# isd_main_lighting_board.net
KiCad netlist of a schematic drawn in EAGLE
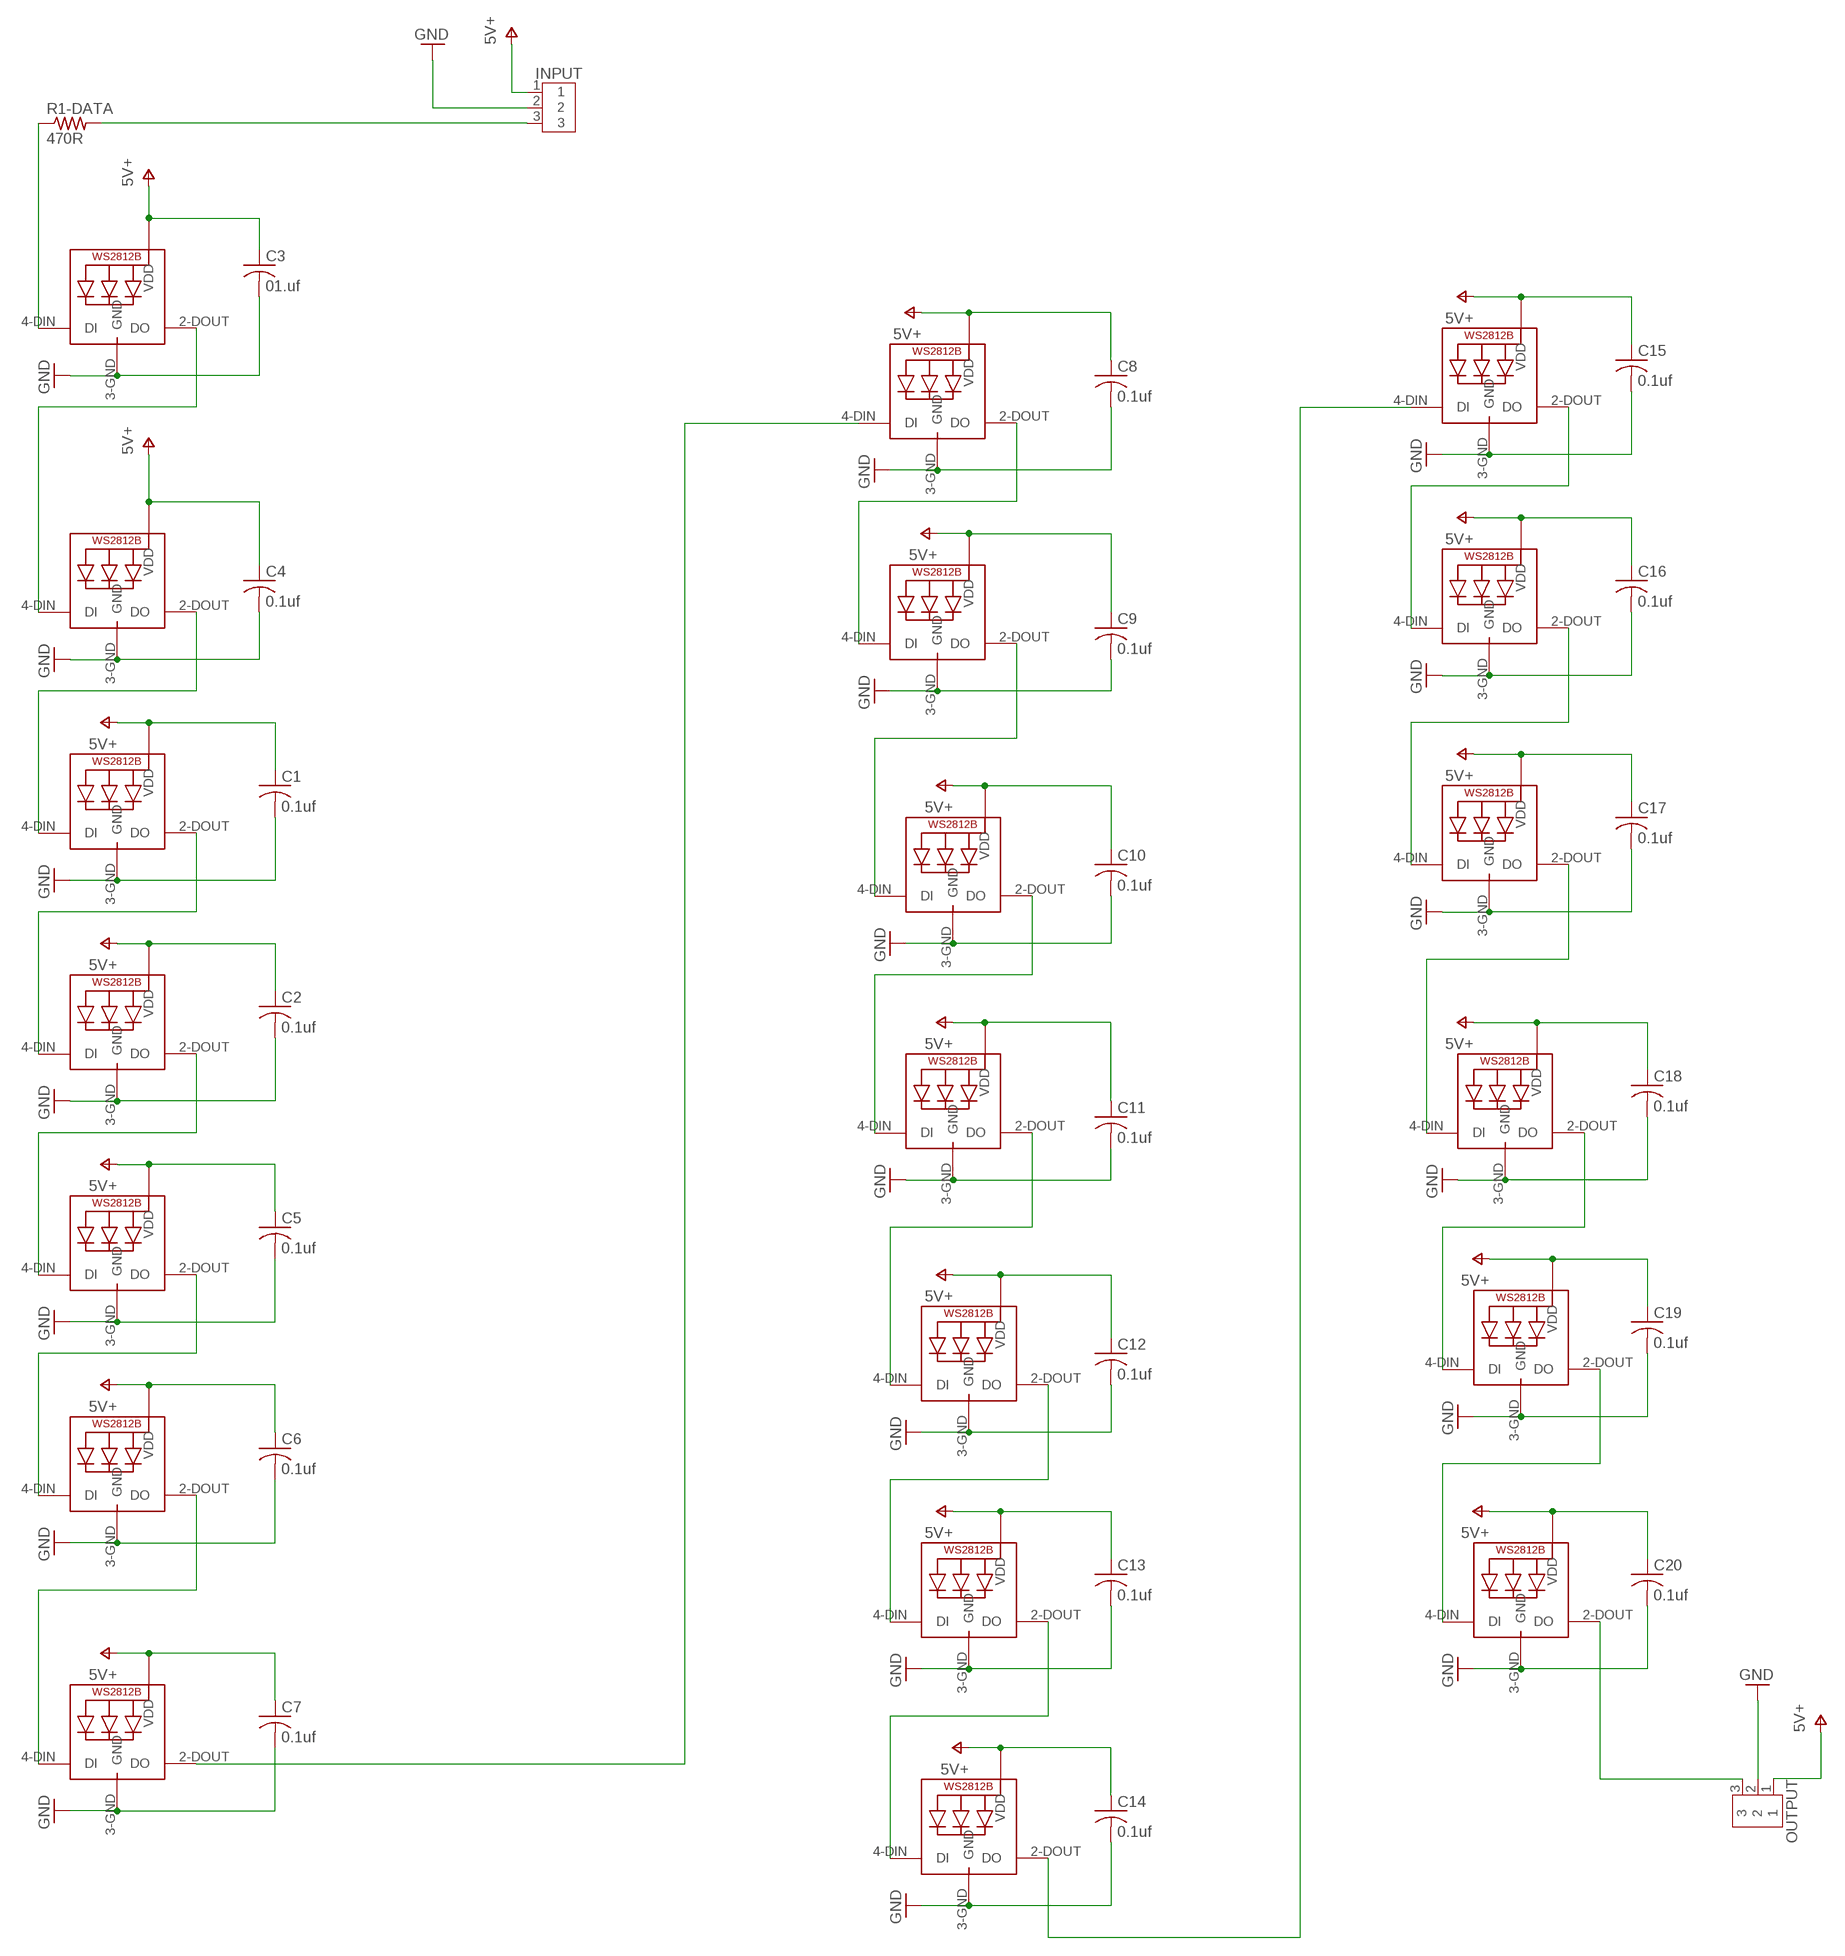
[diagram p0: schematic, sheet 1]

(export (version "E")
  (design (tool "Eeschema 10.0.6"))
  (components
    (comp (ref "C1")
      (value "0.1uf")
      (footprint "eagle-import:C0805K")
      (libsource (lib "eagle-import") (part "C-USC0805K"))
    )
    (comp (ref "C2")
      (value "0.1uf")
      (footprint "eagle-import:C0805K")
      (libsource (lib "eagle-import") (part "C-USC0805K"))
    )
    (comp (ref "C3")
      (value "01.uf")
      (footprint "eagle-import:C0805K")
      (libsource (lib "eagle-import") (part "C-USC0805K"))
    )
    (comp (ref "C4")
      (value "0.1uf")
      (footprint "eagle-import:C0805K")
      (libsource (lib "eagle-import") (part "C-USC0805K"))
    )
    (comp (ref "C5")
      (value "0.1uf")
      (footprint "eagle-import:C0805K")
      (libsource (lib "eagle-import") (part "C-USC0805K"))
    )
    (comp (ref "C6")
      (value "0.1uf")
      (footprint "eagle-import:C0805K")
      (libsource (lib "eagle-import") (part "C-USC0805K"))
    )
    (comp (ref "C7")
      (value "0.1uf")
      (footprint "eagle-import:C0805K")
      (libsource (lib "eagle-import") (part "C-USC0805K"))
    )
    (comp (ref "C8")
      (value "0.1uf")
      (footprint "eagle-import:C0805K")
      (libsource (lib "eagle-import") (part "C-USC0805K"))
    )
    (comp (ref "C9")
      (value "0.1uf")
      (footprint "eagle-import:C0805K")
      (libsource (lib "eagle-import") (part "C-USC0805K"))
    )
    (comp (ref "C10")
      (value "0.1uf")
      (footprint "eagle-import:C0805K")
      (libsource (lib "eagle-import") (part "C-USC0805K"))
    )
    (comp (ref "C11")
      (value "0.1uf")
      (footprint "eagle-import:C0805K")
      (libsource (lib "eagle-import") (part "C-USC0805K"))
    )
    (comp (ref "C12")
      (value "0.1uf")
      (footprint "eagle-import:C0805K")
      (libsource (lib "eagle-import") (part "C-USC0805K"))
    )
    (comp (ref "C13")
      (value "0.1uf")
      (footprint "eagle-import:C0805K")
      (libsource (lib "eagle-import") (part "C-USC0805K"))
    )
    (comp (ref "C14")
      (value "0.1uf")
      (footprint "eagle-import:C0805K")
      (libsource (lib "eagle-import") (part "C-USC0805K"))
    )
    (comp (ref "C15")
      (value "0.1uf")
      (footprint "eagle-import:C0805K")
      (libsource (lib "eagle-import") (part "C-USC0805K"))
    )
    (comp (ref "C16")
      (value "0.1uf")
      (footprint "eagle-import:C0805K")
      (libsource (lib "eagle-import") (part "C-USC0805K"))
    )
    (comp (ref "C17")
      (value "0.1uf")
      (footprint "eagle-import:C0805K")
      (libsource (lib "eagle-import") (part "C-USC0805K"))
    )
    (comp (ref "C18")
      (value "0.1uf")
      (footprint "eagle-import:C0805K")
      (libsource (lib "eagle-import") (part "C-USC0805K"))
    )
    (comp (ref "C19")
      (value "0.1uf")
      (footprint "eagle-import:C0805K")
      (libsource (lib "eagle-import") (part "C-USC0805K"))
    )
    (comp (ref "C20")
      (value "0.1uf")
      (footprint "eagle-import:C0805K")
      (libsource (lib "eagle-import") (part "C-USC0805K"))
    )
    (comp (ref "INPUT")
      (value "B3B-XH-A")
      (footprint "eagle-import:B3B-XH-A")
      (fields (field (name "MANUFACTURER") "JST (XH connector)") (field (name "SPICEPREFIX") "X"))
      (libsource (lib "eagle-import") (part "B3B-XH-A"))
    )
    (comp (ref "OUTPUT")
      (value "B3B-XH-A")
      (footprint "eagle-import:B3B-XH-A")
      (fields (field (name "MANUFACTURER") "JST (XH connector)") (field (name "SPICEPREFIX") "X"))
      (libsource (lib "eagle-import") (part "B3B-XH-A"))
    )
    (comp (ref "R1-DATA")
      (value "470R")
      (footprint "eagle-import:0204_5")
      (fields (field (name "SPICEPREFIX") "R"))
      (libsource (lib "eagle-import") (part "R-US_0204/5"))
    )
    (comp (ref "RGB1")
      (value "WS2812B_5050N")
      (footprint "eagle-import:WS2812B-NARROW")
      (libsource (lib "eagle-import") (part "WS2812B_5050N"))
    )
    (comp (ref "RGB2")
      (value "WS2812B_5050N")
      (footprint "eagle-import:WS2812B-NARROW")
      (fields (field (name "SPICEPREFIX") "E"))
      (libsource (lib "eagle-import") (part "WS2812B_5050N"))
    )
    (comp (ref "RGB3")
      (value "WS2812B_5050N")
      (footprint "eagle-import:WS2812B-NARROW")
      (fields (field (name "SPICEPREFIX") "E"))
      (libsource (lib "eagle-import") (part "WS2812B_5050N"))
    )
    (comp (ref "RGB4")
      (value "WS2812B_5050N")
      (footprint "eagle-import:WS2812B-NARROW")
      (fields (field (name "SPICEPREFIX") "E"))
      (libsource (lib "eagle-import") (part "WS2812B_5050N"))
    )
    (comp (ref "RGB5")
      (value "WS2812B_5050N")
      (footprint "eagle-import:WS2812B-NARROW")
      (fields (field (name "SPICEPREFIX") "E"))
      (libsource (lib "eagle-import") (part "WS2812B_5050N"))
    )
    (comp (ref "RGB6")
      (value "WS2812B_5050N")
      (footprint "eagle-import:WS2812B-NARROW")
      (fields (field (name "SPICEPREFIX") "E"))
      (libsource (lib "eagle-import") (part "WS2812B_5050N"))
    )
    (comp (ref "RGB7")
      (value "WS2812B_5050N")
      (footprint "eagle-import:WS2812B-NARROW")
      (fields (field (name "SPICEPREFIX") "E"))
      (libsource (lib "eagle-import") (part "WS2812B_5050N"))
    )
    (comp (ref "RGB8")
      (value "WS2812B_5050N")
      (footprint "eagle-import:WS2812B-NARROW")
      (fields (field (name "SPICEPREFIX") "E"))
      (libsource (lib "eagle-import") (part "WS2812B_5050N"))
    )
    (comp (ref "RGB9")
      (value "WS2812B_5050N")
      (footprint "eagle-import:WS2812B-NARROW")
      (fields (field (name "SPICEPREFIX") "E"))
      (libsource (lib "eagle-import") (part "WS2812B_5050N"))
    )
    (comp (ref "RGB10")
      (value "WS2812B_5050N")
      (footprint "eagle-import:WS2812B-NARROW")
      (fields (field (name "SPICEPREFIX") "E"))
      (libsource (lib "eagle-import") (part "WS2812B_5050N"))
    )
    (comp (ref "RGB11")
      (value "WS2812B_5050N")
      (footprint "eagle-import:WS2812B-NARROW")
      (fields (field (name "SPICEPREFIX") "E"))
      (libsource (lib "eagle-import") (part "WS2812B_5050N"))
    )
    (comp (ref "RGB12")
      (value "WS2812B_5050N")
      (footprint "eagle-import:WS2812B-NARROW")
      (fields (field (name "SPICEPREFIX") "E"))
      (libsource (lib "eagle-import") (part "WS2812B_5050N"))
    )
    (comp (ref "RGB13")
      (value "WS2812B_5050N")
      (footprint "eagle-import:WS2812B-NARROW")
      (fields (field (name "SPICEPREFIX") "E"))
      (libsource (lib "eagle-import") (part "WS2812B_5050N"))
    )
    (comp (ref "RGB14")
      (value "WS2812B_5050N")
      (footprint "eagle-import:WS2812B-NARROW")
      (fields (field (name "SPICEPREFIX") "E"))
      (libsource (lib "eagle-import") (part "WS2812B_5050N"))
    )
    (comp (ref "RGB15")
      (value "WS2812B_5050N")
      (footprint "eagle-import:WS2812B-NARROW")
      (fields (field (name "SPICEPREFIX") "E"))
      (libsource (lib "eagle-import") (part "WS2812B_5050N"))
    )
    (comp (ref "RGB16")
      (value "WS2812B_5050N")
      (footprint "eagle-import:WS2812B-NARROW")
      (fields (field (name "SPICEPREFIX") "E"))
      (libsource (lib "eagle-import") (part "WS2812B_5050N"))
    )
    (comp (ref "RGB17")
      (value "WS2812B_5050N")
      (footprint "eagle-import:WS2812B-NARROW")
      (fields (field (name "SPICEPREFIX") "E"))
      (libsource (lib "eagle-import") (part "WS2812B_5050N"))
    )
    (comp (ref "RGB18")
      (value "WS2812B_5050N")
      (footprint "eagle-import:WS2812B-NARROW")
      (fields (field (name "SPICEPREFIX") "E"))
      (libsource (lib "eagle-import") (part "WS2812B_5050N"))
    )
    (comp (ref "RGB19")
      (value "WS2812B_5050N")
      (footprint "eagle-import:WS2812B-NARROW")
      (fields (field (name "SPICEPREFIX") "E"))
      (libsource (lib "eagle-import") (part "WS2812B_5050N"))
    )
    (comp (ref "RGB20")
      (value "WS2812B_5050N")
      (footprint "eagle-import:WS2812B-NARROW")
      (fields (field (name "SPICEPREFIX") "E"))
      (libsource (lib "eagle-import") (part "WS2812B_5050N"))
    )
  )
  (nets
    (net (code "1") (name "5V+") (class "Default")
      (node (ref "C1") (pin "1") (pinfunction "1_1") (pintype "passive"))
      (node (ref "C10") (pin "1") (pinfunction "1_1") (pintype "passive"))
      (node (ref "C11") (pin "1") (pinfunction "1_1") (pintype "passive"))
      (node (ref "C12") (pin "1") (pinfunction "1_1") (pintype "passive"))
      (node (ref "C13") (pin "1") (pinfunction "1_1") (pintype "passive"))
      (node (ref "C14") (pin "1") (pinfunction "1_1") (pintype "passive"))
      (node (ref "C15") (pin "1") (pinfunction "1_1") (pintype "passive"))
      (node (ref "C16") (pin "1") (pinfunction "1_1") (pintype "passive"))
      (node (ref "C17") (pin "1") (pinfunction "1_1") (pintype "passive"))
      (node (ref "C18") (pin "1") (pinfunction "1_1") (pintype "passive"))
      (node (ref "C19") (pin "1") (pinfunction "1_1") (pintype "passive"))
      (node (ref "C2") (pin "1") (pinfunction "1_1") (pintype "passive"))
      (node (ref "C20") (pin "1") (pinfunction "1_1") (pintype "passive"))
      (node (ref "C3") (pin "1") (pinfunction "1_1") (pintype "passive"))
      (node (ref "C4") (pin "1") (pinfunction "1_1") (pintype "passive"))
      (node (ref "C5") (pin "1") (pinfunction "1_1") (pintype "passive"))
      (node (ref "C6") (pin "1") (pinfunction "1_1") (pintype "passive"))
      (node (ref "C7") (pin "1") (pinfunction "1_1") (pintype "passive"))
      (node (ref "C8") (pin "1") (pinfunction "1_1") (pintype "passive"))
      (node (ref "C9") (pin "1") (pinfunction "1_1") (pintype "passive"))
      (node (ref "INPUT") (pin "1") (pinfunction "1_1") (pintype "bidirectional"))
      (node (ref "OUTPUT") (pin "1") (pinfunction "1_1") (pintype "bidirectional"))
      (node (ref "RGB1") (pin "1-VDD") (pinfunction "VDD_1-VDD") (pintype "power_in"))
      (node (ref "RGB10") (pin "1-VDD") (pinfunction "VDD_1-VDD") (pintype "power_in"))
      (node (ref "RGB11") (pin "1-VDD") (pinfunction "VDD_1-VDD") (pintype "power_in"))
      (node (ref "RGB12") (pin "1-VDD") (pinfunction "VDD_1-VDD") (pintype "power_in"))
      (node (ref "RGB13") (pin "1-VDD") (pinfunction "VDD_1-VDD") (pintype "power_in"))
      (node (ref "RGB14") (pin "1-VDD") (pinfunction "VDD_1-VDD") (pintype "power_in"))
      (node (ref "RGB15") (pin "1-VDD") (pinfunction "VDD_1-VDD") (pintype "power_in"))
      (node (ref "RGB16") (pin "1-VDD") (pinfunction "VDD_1-VDD") (pintype "power_in"))
      (node (ref "RGB17") (pin "1-VDD") (pinfunction "VDD_1-VDD") (pintype "power_in"))
      (node (ref "RGB18") (pin "1-VDD") (pinfunction "VDD_1-VDD") (pintype "power_in"))
      (node (ref "RGB19") (pin "1-VDD") (pinfunction "VDD_1-VDD") (pintype "power_in"))
      (node (ref "RGB2") (pin "1-VDD") (pinfunction "VDD_1-VDD") (pintype "power_in"))
      (node (ref "RGB20") (pin "1-VDD") (pinfunction "VDD_1-VDD") (pintype "power_in"))
      (node (ref "RGB3") (pin "1-VDD") (pinfunction "VDD_1-VDD") (pintype "power_in"))
      (node (ref "RGB4") (pin "1-VDD") (pinfunction "VDD_1-VDD") (pintype "power_in"))
      (node (ref "RGB5") (pin "1-VDD") (pinfunction "VDD_1-VDD") (pintype "power_in"))
      (node (ref "RGB6") (pin "1-VDD") (pinfunction "VDD_1-VDD") (pintype "power_in"))
      (node (ref "RGB7") (pin "1-VDD") (pinfunction "VDD_1-VDD") (pintype "power_in"))
      (node (ref "RGB8") (pin "1-VDD") (pinfunction "VDD_1-VDD") (pintype "power_in"))
      (node (ref "RGB9") (pin "1-VDD") (pinfunction "VDD_1-VDD") (pintype "power_in"))
    )
    (net (code "2") (name "GND") (class "Default")
      (node (ref "C1") (pin "2") (pinfunction "2_2") (pintype "passive"))
      (node (ref "C10") (pin "2") (pinfunction "2_2") (pintype "passive"))
      (node (ref "C11") (pin "2") (pinfunction "2_2") (pintype "passive"))
      (node (ref "C12") (pin "2") (pinfunction "2_2") (pintype "passive"))
      (node (ref "C13") (pin "2") (pinfunction "2_2") (pintype "passive"))
      (node (ref "C14") (pin "2") (pinfunction "2_2") (pintype "passive"))
      (node (ref "C15") (pin "2") (pinfunction "2_2") (pintype "passive"))
      (node (ref "C16") (pin "2") (pinfunction "2_2") (pintype "passive"))
      (node (ref "C17") (pin "2") (pinfunction "2_2") (pintype "passive"))
      (node (ref "C18") (pin "2") (pinfunction "2_2") (pintype "passive"))
      (node (ref "C19") (pin "2") (pinfunction "2_2") (pintype "passive"))
      (node (ref "C2") (pin "2") (pinfunction "2_2") (pintype "passive"))
      (node (ref "C20") (pin "2") (pinfunction "2_2") (pintype "passive"))
      (node (ref "C3") (pin "2") (pinfunction "2_2") (pintype "passive"))
      (node (ref "C4") (pin "2") (pinfunction "2_2") (pintype "passive"))
      (node (ref "C5") (pin "2") (pinfunction "2_2") (pintype "passive"))
      (node (ref "C6") (pin "2") (pinfunction "2_2") (pintype "passive"))
      (node (ref "C7") (pin "2") (pinfunction "2_2") (pintype "passive"))
      (node (ref "C8") (pin "2") (pinfunction "2_2") (pintype "passive"))
      (node (ref "C9") (pin "2") (pinfunction "2_2") (pintype "passive"))
      (node (ref "INPUT") (pin "2") (pinfunction "2_2") (pintype "bidirectional"))
      (node (ref "OUTPUT") (pin "2") (pinfunction "2_2") (pintype "bidirectional"))
      (node (ref "RGB1") (pin "3-GND") (pinfunction "GND_3-GND") (pintype "power_in"))
      (node (ref "RGB10") (pin "3-GND") (pinfunction "GND_3-GND") (pintype "power_in"))
      (node (ref "RGB11") (pin "3-GND") (pinfunction "GND_3-GND") (pintype "power_in"))
      (node (ref "RGB12") (pin "3-GND") (pinfunction "GND_3-GND") (pintype "power_in"))
      (node (ref "RGB13") (pin "3-GND") (pinfunction "GND_3-GND") (pintype "power_in"))
      (node (ref "RGB14") (pin "3-GND") (pinfunction "GND_3-GND") (pintype "power_in"))
      (node (ref "RGB15") (pin "3-GND") (pinfunction "GND_3-GND") (pintype "power_in"))
      (node (ref "RGB16") (pin "3-GND") (pinfunction "GND_3-GND") (pintype "power_in"))
      (node (ref "RGB17") (pin "3-GND") (pinfunction "GND_3-GND") (pintype "power_in"))
      (node (ref "RGB18") (pin "3-GND") (pinfunction "GND_3-GND") (pintype "power_in"))
      (node (ref "RGB19") (pin "3-GND") (pinfunction "GND_3-GND") (pintype "power_in"))
      (node (ref "RGB2") (pin "3-GND") (pinfunction "GND_3-GND") (pintype "power_in"))
      (node (ref "RGB20") (pin "3-GND") (pinfunction "GND_3-GND") (pintype "power_in"))
      (node (ref "RGB3") (pin "3-GND") (pinfunction "GND_3-GND") (pintype "power_in"))
      (node (ref "RGB4") (pin "3-GND") (pinfunction "GND_3-GND") (pintype "power_in"))
      (node (ref "RGB5") (pin "3-GND") (pinfunction "GND_3-GND") (pintype "power_in"))
      (node (ref "RGB6") (pin "3-GND") (pinfunction "GND_3-GND") (pintype "power_in"))
      (node (ref "RGB7") (pin "3-GND") (pinfunction "GND_3-GND") (pintype "power_in"))
      (node (ref "RGB8") (pin "3-GND") (pinfunction "GND_3-GND") (pintype "power_in"))
      (node (ref "RGB9") (pin "3-GND") (pinfunction "GND_3-GND") (pintype "power_in"))
    )
    (net (code "3") (name "Net-(INPUT-Pad3)") (class "Default")
      (node (ref "INPUT") (pin "3") (pinfunction "3_3") (pintype "bidirectional"))
      (node (ref "R1-DATA") (pin "2") (pinfunction "2_2") (pintype "passive"))
    )
    (net (code "4") (name "Net-(RGB1-DI)") (class "Default")
      (node (ref "R1-DATA") (pin "1") (pinfunction "1_1") (pintype "passive"))
      (node (ref "RGB1") (pin "4-DIN") (pinfunction "DI_4-DIN") (pintype "input"))
    )
    (net (code "5") (name "Net-(RGB1-DO)") (class "Default")
      (node (ref "RGB1") (pin "2-DOUT") (pinfunction "DO_2-DOUT") (pintype "output"))
      (node (ref "RGB2") (pin "4-DIN") (pinfunction "DI_4-DIN") (pintype "input"))
    )
    (net (code "6") (name "Net-(RGB2-DO)") (class "Default")
      (node (ref "RGB2") (pin "2-DOUT") (pinfunction "DO_2-DOUT") (pintype "output"))
      (node (ref "RGB3") (pin "4-DIN") (pinfunction "DI_4-DIN") (pintype "input"))
    )
    (net (code "7") (name "Net-(RGB3-DO)") (class "Default")
      (node (ref "RGB3") (pin "2-DOUT") (pinfunction "DO_2-DOUT") (pintype "output"))
      (node (ref "RGB4") (pin "4-DIN") (pinfunction "DI_4-DIN") (pintype "input"))
    )
    (net (code "8") (name "Net-(RGB4-DO)") (class "Default")
      (node (ref "RGB4") (pin "2-DOUT") (pinfunction "DO_2-DOUT") (pintype "output"))
      (node (ref "RGB5") (pin "4-DIN") (pinfunction "DI_4-DIN") (pintype "input"))
    )
    (net (code "9") (name "Net-(RGB5-DO)") (class "Default")
      (node (ref "RGB5") (pin "2-DOUT") (pinfunction "DO_2-DOUT") (pintype "output"))
      (node (ref "RGB6") (pin "4-DIN") (pinfunction "DI_4-DIN") (pintype "input"))
    )
    (net (code "10") (name "Net-(RGB6-DO)") (class "Default")
      (node (ref "RGB6") (pin "2-DOUT") (pinfunction "DO_2-DOUT") (pintype "output"))
      (node (ref "RGB7") (pin "4-DIN") (pinfunction "DI_4-DIN") (pintype "input"))
    )
    (net (code "11") (name "Net-(RGB7-DO)") (class "Default")
      (node (ref "RGB7") (pin "2-DOUT") (pinfunction "DO_2-DOUT") (pintype "output"))
      (node (ref "RGB8") (pin "4-DIN") (pinfunction "DI_4-DIN") (pintype "input"))
    )
    (net (code "12") (name "Net-(RGB8-DO)") (class "Default")
      (node (ref "RGB8") (pin "2-DOUT") (pinfunction "DO_2-DOUT") (pintype "output"))
      (node (ref "RGB9") (pin "4-DIN") (pinfunction "DI_4-DIN") (pintype "input"))
    )
    (net (code "13") (name "Net-(RGB10-DI)") (class "Default")
      (node (ref "RGB10") (pin "4-DIN") (pinfunction "DI_4-DIN") (pintype "input"))
      (node (ref "RGB9") (pin "2-DOUT") (pinfunction "DO_2-DOUT") (pintype "output"))
    )
    (net (code "14") (name "Net-(RGB10-DO)") (class "Default")
      (node (ref "RGB10") (pin "2-DOUT") (pinfunction "DO_2-DOUT") (pintype "output"))
      (node (ref "RGB11") (pin "4-DIN") (pinfunction "DI_4-DIN") (pintype "input"))
    )
    (net (code "15") (name "Net-(RGB11-DO)") (class "Default")
      (node (ref "RGB11") (pin "2-DOUT") (pinfunction "DO_2-DOUT") (pintype "output"))
      (node (ref "RGB12") (pin "4-DIN") (pinfunction "DI_4-DIN") (pintype "input"))
    )
    (net (code "16") (name "Net-(RGB12-DO)") (class "Default")
      (node (ref "RGB12") (pin "2-DOUT") (pinfunction "DO_2-DOUT") (pintype "output"))
      (node (ref "RGB13") (pin "4-DIN") (pinfunction "DI_4-DIN") (pintype "input"))
    )
    (net (code "17") (name "Net-(RGB13-DO)") (class "Default")
      (node (ref "RGB13") (pin "2-DOUT") (pinfunction "DO_2-DOUT") (pintype "output"))
      (node (ref "RGB14") (pin "4-DIN") (pinfunction "DI_4-DIN") (pintype "input"))
    )
    (net (code "18") (name "Net-(RGB14-DO)") (class "Default")
      (node (ref "RGB14") (pin "2-DOUT") (pinfunction "DO_2-DOUT") (pintype "output"))
      (node (ref "RGB15") (pin "4-DIN") (pinfunction "DI_4-DIN") (pintype "input"))
    )
    (net (code "19") (name "Net-(RGB15-DO)") (class "Default")
      (node (ref "RGB15") (pin "2-DOUT") (pinfunction "DO_2-DOUT") (pintype "output"))
      (node (ref "RGB16") (pin "4-DIN") (pinfunction "DI_4-DIN") (pintype "input"))
    )
    (net (code "20") (name "Net-(RGB16-DO)") (class "Default")
      (node (ref "RGB16") (pin "2-DOUT") (pinfunction "DO_2-DOUT") (pintype "output"))
      (node (ref "RGB17") (pin "4-DIN") (pinfunction "DI_4-DIN") (pintype "input"))
    )
    (net (code "21") (name "Net-(RGB17-DO)") (class "Default")
      (node (ref "RGB17") (pin "2-DOUT") (pinfunction "DO_2-DOUT") (pintype "output"))
      (node (ref "RGB18") (pin "4-DIN") (pinfunction "DI_4-DIN") (pintype "input"))
    )
    (net (code "22") (name "Net-(RGB18-DO)") (class "Default")
      (node (ref "RGB18") (pin "2-DOUT") (pinfunction "DO_2-DOUT") (pintype "output"))
      (node (ref "RGB19") (pin "4-DIN") (pinfunction "DI_4-DIN") (pintype "input"))
    )
    (net (code "23") (name "Net-(RGB19-DO)") (class "Default")
      (node (ref "RGB19") (pin "2-DOUT") (pinfunction "DO_2-DOUT") (pintype "output"))
      (node (ref "RGB20") (pin "4-DIN") (pinfunction "DI_4-DIN") (pintype "input"))
    )
    (net (code "24") (name "Net-(RGB20-DO)") (class "Default")
      (node (ref "OUTPUT") (pin "3") (pinfunction "3_3") (pintype "bidirectional"))
      (node (ref "RGB20") (pin "2-DOUT") (pinfunction "DO_2-DOUT") (pintype "output"))
    )
  )
)
